# mp34dt05.net
KiCad netlist of a schematic drawn in EAGLE
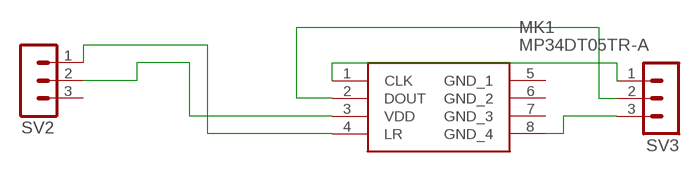
[diagram p0: schematic, sheet 1]

(export (version "E")
  (design (tool "Eeschema 10.0.6"))
  (components
    (comp (ref "MK1")
      (value "MP34DT05TR-A")
      (footprint "eagle-import:MP34DT05TRA")
      (fields (field (name "MOUSER_PART_NUMBER") "511-MP34DT05TR-A"))
      (libsource (lib "eagle-import") (part "MP34DT05TR-A"))
    )
    (comp (ref "SV2")
      (value "MA03-1")
      (footprint "eagle-import:MA03-1")
      (libsource (lib "eagle-import") (part "MA03-1"))
    )
    (comp (ref "SV3")
      (value "MA03-1")
      (footprint "eagle-import:MA03-1")
      (libsource (lib "eagle-import") (part "MA03-1"))
    )
  )
  (nets
    (net (code "1") (name "Net-(MK1-CLK)") (class "Default")
      (node (ref "MK1") (pin "1") (pinfunction "CLK_1") (pintype "bidirectional"))
      (node (ref "SV3") (pin "1") (pinfunction "1_1") (pintype "passive"))
    )
    (net (code "2") (name "Net-(MK1-DOUT)") (class "Default")
      (node (ref "MK1") (pin "2") (pinfunction "DOUT_2") (pintype "bidirectional"))
      (node (ref "SV3") (pin "2") (pinfunction "2_2") (pintype "passive"))
    )
    (net (code "3") (name "Net-(MK1-GND_4)") (class "Default")
      (node (ref "MK1") (pin "8") (pinfunction "GND_4_8") (pintype "bidirectional"))
      (node (ref "SV3") (pin "3") (pinfunction "3_3") (pintype "passive"))
    )
    (net (code "4") (name "Net-(MK1-LR)") (class "Default")
      (node (ref "MK1") (pin "4") (pinfunction "LR_4") (pintype "bidirectional"))
      (node (ref "SV2") (pin "1") (pinfunction "1_1") (pintype "passive"))
    )
    (net (code "5") (name "Net-(MK1-VDD)") (class "Default")
      (node (ref "MK1") (pin "3") (pinfunction "VDD_3") (pintype "bidirectional"))
      (node (ref "SV2") (pin "2") (pinfunction "2_2") (pintype "passive"))
    )
    (net (code "6") (name "unconnected-(MK1-GND_1-Pad5)") (class "Default")
      (node (ref "MK1") (pin "5") (pinfunction "GND_1_5") (pintype "bidirectional"))
    )
    (net (code "7") (name "unconnected-(MK1-GND_2-Pad6)") (class "Default")
      (node (ref "MK1") (pin "6") (pinfunction "GND_2_6") (pintype "bidirectional"))
    )
    (net (code "8") (name "unconnected-(MK1-GND_3-Pad7)") (class "Default")
      (node (ref "MK1") (pin "7") (pinfunction "GND_3_7") (pintype "bidirectional"))
    )
    (net (code "9") (name "unconnected-(SV2-Pad3)") (class "Default")
      (node (ref "SV2") (pin "3") (pinfunction "3_3") (pintype "passive"))
    )
  )
)
